# sfp-board.net
KiCad netlist of a schematic drawn in EAGLE
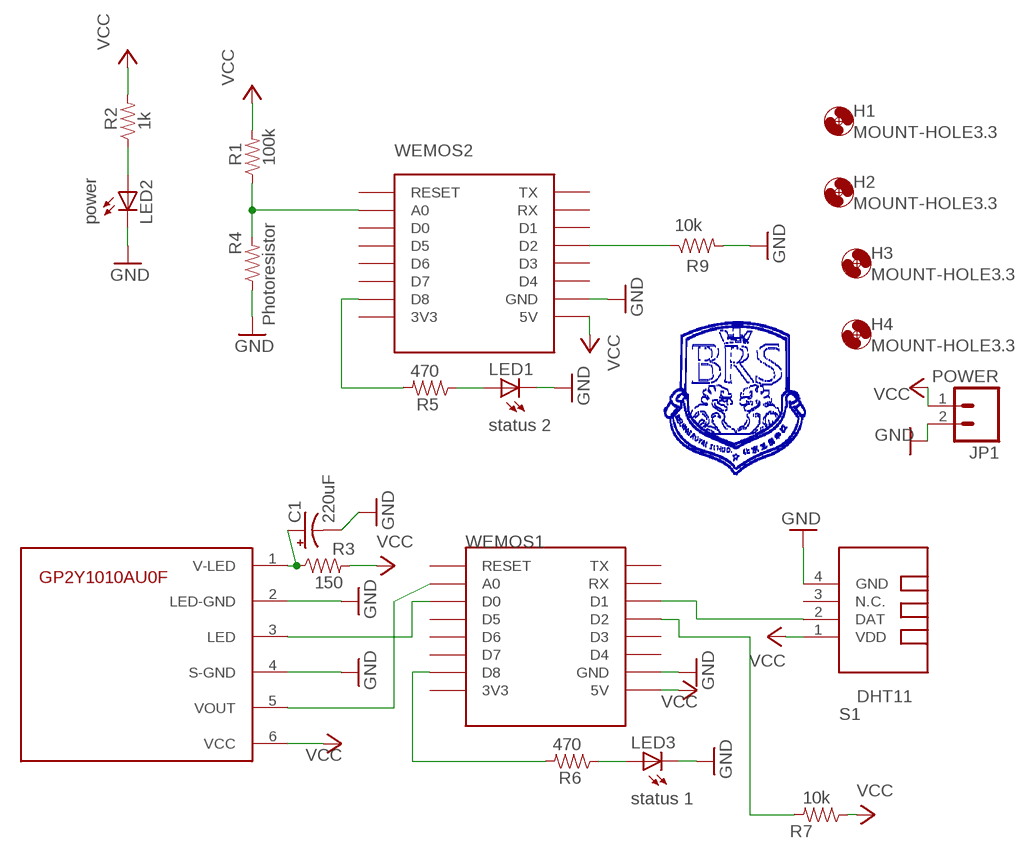
[diagram p0: schematic, sheet 1]

(export (version "E")
  (design (tool "Eeschema 10.0.6"))
  (components
    (comp (ref "C1")
      (value "220uF")
      (footprint "eagle-import:CPOL-RADIAL-100UF-25V")
      (libsource (lib "eagle-import") (part "CAP_POLPTH1"))
    )
    (comp (ref "GP2Y1010AU0F")
      (value "GP2Y1010AU")
      (footprint "eagle-import:GP2Y1010AU")
      (libsource (lib "eagle-import") (part "GP2Y1010AU"))
    )
    (comp (ref "H1")
      (value "MOUNT-HOLE3.3")
      (footprint "eagle-import:3,3")
      (libsource (lib "eagle-import") (part "MOUNT-HOLE3.3"))
    )
    (comp (ref "H2")
      (value "MOUNT-HOLE3.3")
      (footprint "eagle-import:3,3")
      (libsource (lib "eagle-import") (part "MOUNT-HOLE3.3"))
    )
    (comp (ref "H3")
      (value "MOUNT-HOLE3.3")
      (footprint "eagle-import:3,3")
      (libsource (lib "eagle-import") (part "MOUNT-HOLE3.3"))
    )
    (comp (ref "H4")
      (value "MOUNT-HOLE3.3")
      (footprint "eagle-import:3,3")
      (libsource (lib "eagle-import") (part "MOUNT-HOLE3.3"))
    )
    (comp (ref "JP1")
      (value "POWER")
      (footprint "eagle-import:1X02_LONGPADS")
      (libsource (lib "eagle-import") (part "M02PTH3"))
    )
    (comp (ref "LED1")
      (value "status 2")
      (footprint "eagle-import:LED5MM")
      (libsource (lib "eagle-import") (part "LED5MM"))
    )
    (comp (ref "LED2")
      (value "power")
      (footprint "eagle-import:LED5MM")
      (libsource (lib "eagle-import") (part "LED5MM"))
    )
    (comp (ref "LED3")
      (value "status 1")
      (footprint "eagle-import:LED5MM")
      (libsource (lib "eagle-import") (part "LED5MM"))
    )
    (comp (ref "R1")
      (value "100k")
      (footprint "eagle-import:0414_15")
      (libsource (lib "eagle-import") (part "RESISTOR0414/15"))
    )
    (comp (ref "R2")
      (value "1k")
      (footprint "eagle-import:0414_15")
      (libsource (lib "eagle-import") (part "RESISTOR0414/15"))
    )
    (comp (ref "R3")
      (value "150")
      (footprint "eagle-import:0414_15")
      (libsource (lib "eagle-import") (part "RESISTOR0414/15"))
    )
    (comp (ref "R4")
      (value "Photoresistor")
      (footprint "eagle-import:0414V")
      (libsource (lib "eagle-import") (part "RESISTOR0414V"))
    )
    (comp (ref "R5")
      (value "470")
      (footprint "eagle-import:0414_15")
      (libsource (lib "eagle-import") (part "RESISTOR0414/15"))
    )
    (comp (ref "R6")
      (value "470")
      (footprint "eagle-import:0414_15")
      (libsource (lib "eagle-import") (part "RESISTOR0414/15"))
    )
    (comp (ref "R7")
      (value "10k")
      (footprint "eagle-import:0414_15")
      (libsource (lib "eagle-import") (part "RESISTOR0414/15"))
    )
    (comp (ref "R9")
      (value "10k")
      (footprint "eagle-import:0414_15")
      (libsource (lib "eagle-import") (part "RESISTOR0414/15"))
    )
    (comp (ref "S1")
      (value "DHT11")
      (footprint "eagle-import:TEMP-HUM-SENSOR-DHT11")
      (libsource (lib "eagle-import") (part "TEMP-HUM-SENSOR-DHT11"))
    )
    (comp (ref "U$1")
      (value "BRS-SYMBOL")
      (footprint "eagle-import:BRS")
      (libsource (lib "eagle-import") (part "BRS-SYMBOL"))
    )
    (comp (ref "WEMOS1")
      (value "WEMOS-D1-MINI")
      (footprint "eagle-import:WEMOS-D1-MINI")
      (libsource (lib "eagle-import") (part "WEMOS-D1-MINI"))
    )
    (comp (ref "WEMOS2")
      (value "WEMOS-D1-MINI")
      (footprint "eagle-import:WEMOS-D1-MINI")
      (libsource (lib "eagle-import") (part "WEMOS-D1-MINI"))
    )
  )
  (nets
    (net (code "1") (name "GND") (class "Default")
      (node (ref "C1") (pin "2") (pinfunction "-_2") (pintype "passive"))
      (node (ref "GP2Y1010AU0F") (pin "2") (pinfunction "LED-GND_2") (pintype "power_in"))
      (node (ref "GP2Y1010AU0F") (pin "4") (pinfunction "S-GND_4") (pintype "power_in"))
      (node (ref "JP1") (pin "2") (pinfunction "2_2") (pintype "passive"))
      (node (ref "LED1") (pin "K") (pinfunction "C_K") (pintype "passive"))
      (node (ref "LED2") (pin "K") (pinfunction "C_K") (pintype "passive"))
      (node (ref "LED3") (pin "K") (pinfunction "C_K") (pintype "passive"))
      (node (ref "R4") (pin "1") (pinfunction "1_1") (pintype "passive"))
      (node (ref "R9") (pin "2") (pinfunction "2_2") (pintype "passive"))
      (node (ref "S1") (pin "4") (pinfunction "GND_4") (pintype "power_in"))
      (node (ref "WEMOS1") (pin "GND") (pinfunction "GND_GND") (pintype "bidirectional"))
      (node (ref "WEMOS2") (pin "GND") (pinfunction "GND_GND") (pintype "bidirectional"))
    )
    (net (code "2") (name "Net-(C1-+)") (class "Default")
      (node (ref "C1") (pin "1") (pinfunction "+_1") (pintype "passive"))
      (node (ref "GP2Y1010AU0F") (pin "1") (pinfunction "V-LED_1") (pintype "power_in"))
      (node (ref "R3") (pin "1") (pinfunction "1_1") (pintype "passive"))
    )
    (net (code "3") (name "Net-(GP2Y1010AU0F-LED)") (class "Default")
      (node (ref "GP2Y1010AU0F") (pin "3") (pinfunction "LED_3") (pintype "input"))
      (node (ref "WEMOS1") (pin "D0") (pinfunction "D0_D0") (pintype "bidirectional"))
    )
    (net (code "4") (name "Net-(GP2Y1010AU0F-VOUT)") (class "Default")
      (node (ref "GP2Y1010AU0F") (pin "5") (pinfunction "VOUT_5") (pintype "output"))
      (node (ref "WEMOS1") (pin "A0") (pinfunction "A0_A0") (pintype "bidirectional"))
    )
    (net (code "5") (name "Net-(LED1-PadA)") (class "Default")
      (node (ref "LED1") (pin "A") (pinfunction "A_A") (pintype "passive"))
      (node (ref "R5") (pin "1") (pinfunction "1_1") (pintype "passive"))
    )
    (net (code "6") (name "Net-(LED2-PadA)") (class "Default")
      (node (ref "LED2") (pin "A") (pinfunction "A_A") (pintype "passive"))
      (node (ref "R2") (pin "1") (pinfunction "1_1") (pintype "passive"))
    )
    (net (code "7") (name "Net-(LED3-PadA)") (class "Default")
      (node (ref "LED3") (pin "A") (pinfunction "A_A") (pintype "passive"))
      (node (ref "R6") (pin "1") (pinfunction "1_1") (pintype "passive"))
    )
    (net (code "8") (name "Net-(R1-Pad1)") (class "Default")
      (node (ref "R1") (pin "1") (pinfunction "1_1") (pintype "passive"))
      (node (ref "R4") (pin "2") (pinfunction "2_2") (pintype "passive"))
      (node (ref "WEMOS2") (pin "A0") (pinfunction "A0_A0") (pintype "bidirectional"))
    )
    (net (code "9") (name "Net-(R5-Pad2)") (class "Default")
      (node (ref "R5") (pin "2") (pinfunction "2_2") (pintype "passive"))
      (node (ref "WEMOS2") (pin "D8") (pinfunction "D8_D8") (pintype "bidirectional"))
    )
    (net (code "10") (name "Net-(R6-Pad2)") (class "Default")
      (node (ref "R6") (pin "2") (pinfunction "2_2") (pintype "passive"))
      (node (ref "WEMOS1") (pin "D8") (pinfunction "D8_D8") (pintype "bidirectional"))
    )
    (net (code "11") (name "Net-(R7-Pad2)") (class "Default")
      (node (ref "R7") (pin "2") (pinfunction "2_2") (pintype "passive"))
      (node (ref "WEMOS1") (pin "D2") (pinfunction "D2_D2") (pintype "bidirectional"))
    )
    (net (code "12") (name "Net-(R9-Pad1)") (class "Default")
      (node (ref "R9") (pin "1") (pinfunction "1_1") (pintype "passive"))
      (node (ref "WEMOS2") (pin "D2") (pinfunction "D2_D2") (pintype "bidirectional"))
    )
    (net (code "13") (name "Net-(S1-DAT)") (class "Default")
      (node (ref "S1") (pin "2") (pinfunction "DAT_2") (pintype "bidirectional"))
      (node (ref "WEMOS1") (pin "D1") (pinfunction "D1_D1") (pintype "bidirectional"))
    )
    (net (code "14") (name "VCC") (class "Default")
      (node (ref "GP2Y1010AU0F") (pin "6") (pinfunction "VCC_6") (pintype "power_in"))
      (node (ref "JP1") (pin "1") (pinfunction "1_1") (pintype "passive"))
      (node (ref "R1") (pin "2") (pinfunction "2_2") (pintype "passive"))
      (node (ref "R2") (pin "2") (pinfunction "2_2") (pintype "passive"))
      (node (ref "R3") (pin "2") (pinfunction "2_2") (pintype "passive"))
      (node (ref "R7") (pin "1") (pinfunction "1_1") (pintype "passive"))
      (node (ref "S1") (pin "1") (pinfunction "VDD_1") (pintype "power_in"))
      (node (ref "WEMOS1") (pin "5V") (pinfunction "5V_5V") (pintype "bidirectional"))
      (node (ref "WEMOS2") (pin "5V") (pinfunction "5V_5V") (pintype "bidirectional"))
    )
    (net (code "15") (name "unconnected-(S1-N.C.-Pad3)") (class "Default")
      (node (ref "S1") (pin "3") (pinfunction "N.C._3") (pintype "passive"))
    )
    (net (code "16") (name "unconnected-(WEMOS1-Pad3V3)") (class "Default")
      (node (ref "WEMOS1") (pin "3V3") (pinfunction "3V3_3V3") (pintype "bidirectional"))
    )
    (net (code "17") (name "unconnected-(WEMOS1-PadD3)") (class "Default")
      (node (ref "WEMOS1") (pin "D3") (pinfunction "D3_D3") (pintype "bidirectional"))
    )
    (net (code "18") (name "unconnected-(WEMOS1-PadD4)") (class "Default")
      (node (ref "WEMOS1") (pin "D4") (pinfunction "D4_D4") (pintype "bidirectional"))
    )
    (net (code "19") (name "unconnected-(WEMOS1-PadD5)") (class "Default")
      (node (ref "WEMOS1") (pin "D5") (pinfunction "D5_D5") (pintype "bidirectional"))
    )
    (net (code "20") (name "unconnected-(WEMOS1-PadD6)") (class "Default")
      (node (ref "WEMOS1") (pin "D6") (pinfunction "D6_D6") (pintype "bidirectional"))
    )
    (net (code "21") (name "unconnected-(WEMOS1-PadD7)") (class "Default")
      (node (ref "WEMOS1") (pin "D7") (pinfunction "D7_D7") (pintype "bidirectional"))
    )
    (net (code "22") (name "unconnected-(WEMOS1-PadRESET)") (class "Default")
      (node (ref "WEMOS1") (pin "RESET") (pinfunction "RESET_RESET") (pintype "bidirectional"))
    )
    (net (code "23") (name "unconnected-(WEMOS1-PadRX)") (class "Default")
      (node (ref "WEMOS1") (pin "RX") (pinfunction "RX_RX") (pintype "bidirectional"))
    )
    (net (code "24") (name "unconnected-(WEMOS1-PadTX)") (class "Default")
      (node (ref "WEMOS1") (pin "TX") (pinfunction "TX_TX") (pintype "bidirectional"))
    )
    (net (code "25") (name "unconnected-(WEMOS2-Pad3V3)") (class "Default")
      (node (ref "WEMOS2") (pin "3V3") (pinfunction "3V3_3V3") (pintype "bidirectional"))
    )
    (net (code "26") (name "unconnected-(WEMOS2-PadD0)") (class "Default")
      (node (ref "WEMOS2") (pin "D0") (pinfunction "D0_D0") (pintype "bidirectional"))
    )
    (net (code "27") (name "unconnected-(WEMOS2-PadD1)") (class "Default")
      (node (ref "WEMOS2") (pin "D1") (pinfunction "D1_D1") (pintype "bidirectional"))
    )
    (net (code "28") (name "unconnected-(WEMOS2-PadD3)") (class "Default")
      (node (ref "WEMOS2") (pin "D3") (pinfunction "D3_D3") (pintype "bidirectional"))
    )
    (net (code "29") (name "unconnected-(WEMOS2-PadD4)") (class "Default")
      (node (ref "WEMOS2") (pin "D4") (pinfunction "D4_D4") (pintype "bidirectional"))
    )
    (net (code "30") (name "unconnected-(WEMOS2-PadD5)") (class "Default")
      (node (ref "WEMOS2") (pin "D5") (pinfunction "D5_D5") (pintype "bidirectional"))
    )
    (net (code "31") (name "unconnected-(WEMOS2-PadD6)") (class "Default")
      (node (ref "WEMOS2") (pin "D6") (pinfunction "D6_D6") (pintype "bidirectional"))
    )
    (net (code "32") (name "unconnected-(WEMOS2-PadD7)") (class "Default")
      (node (ref "WEMOS2") (pin "D7") (pinfunction "D7_D7") (pintype "bidirectional"))
    )
    (net (code "33") (name "unconnected-(WEMOS2-PadRESET)") (class "Default")
      (node (ref "WEMOS2") (pin "RESET") (pinfunction "RESET_RESET") (pintype "bidirectional"))
    )
    (net (code "34") (name "unconnected-(WEMOS2-PadRX)") (class "Default")
      (node (ref "WEMOS2") (pin "RX") (pinfunction "RX_RX") (pintype "bidirectional"))
    )
    (net (code "35") (name "unconnected-(WEMOS2-PadTX)") (class "Default")
      (node (ref "WEMOS2") (pin "TX") (pinfunction "TX_TX") (pintype "bidirectional"))
    )
  )
)
